# feather_stm32f1.net
KiCad netlist of a schematic drawn in EAGLE
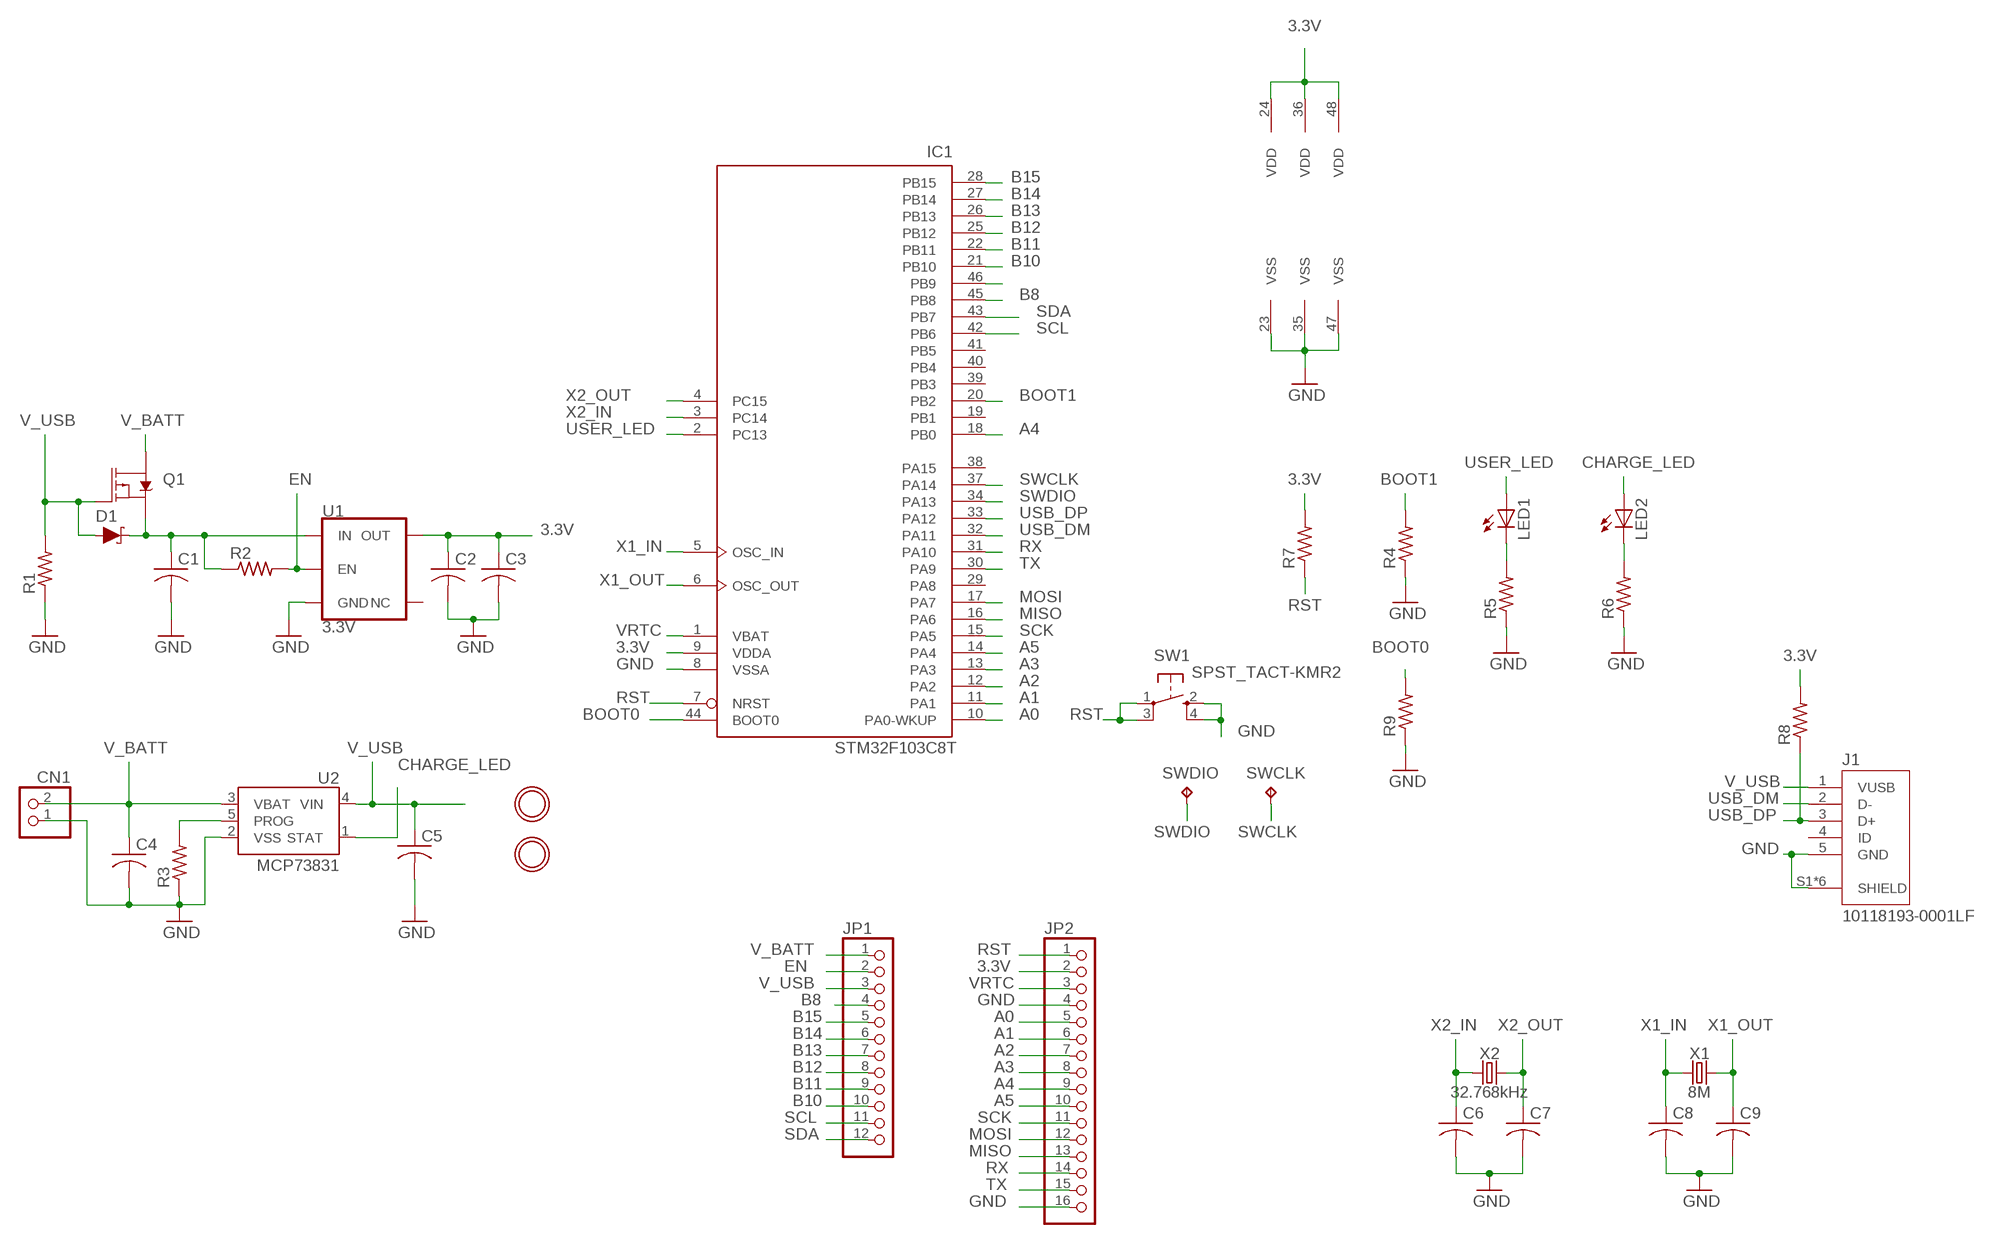
[diagram p0: schematic, sheet 1]

(export (version "E")
  (design (tool "Eeschema 10.0.6"))
  (components
    (comp (ref "C1")
      (value "C-USC0805")
      (footprint "eagle-import:C0805")
      (libsource (lib "eagle-import") (part "C-USC0805"))
    )
    (comp (ref "C2")
      (value "C-USC0805")
      (footprint "eagle-import:C0805")
      (libsource (lib "eagle-import") (part "C-USC0805"))
    )
    (comp (ref "C3")
      (value "C-USC0805")
      (footprint "eagle-import:C0805")
      (libsource (lib "eagle-import") (part "C-USC0805"))
    )
    (comp (ref "C4")
      (value "C-USC0805")
      (footprint "eagle-import:C0805")
      (libsource (lib "eagle-import") (part "C-USC0805"))
    )
    (comp (ref "C5")
      (value "C-USC0805")
      (footprint "eagle-import:C0805")
      (libsource (lib "eagle-import") (part "C-USC0805"))
    )
    (comp (ref "C6")
      (value "C-USC0603")
      (footprint "eagle-import:C0603")
      (libsource (lib "eagle-import") (part "C-USC0603"))
    )
    (comp (ref "C7")
      (value "C-USC0603")
      (footprint "eagle-import:C0603")
      (libsource (lib "eagle-import") (part "C-USC0603"))
    )
    (comp (ref "C8")
      (value "C-USC0603")
      (footprint "eagle-import:C0603")
      (libsource (lib "eagle-import") (part "C-USC0603"))
    )
    (comp (ref "C9")
      (value "C-USC0603")
      (footprint "eagle-import:C0603")
      (libsource (lib "eagle-import") (part "C-USC0603"))
    )
    (comp (ref "CN1")
      (value "JST_2PIN-SMT-RA")
      (footprint "eagle-import:JST-PH-2-SMT-RA")
      (libsource (lib "eagle-import") (part "JST_2PIN-SMT-RA"))
    )
    (comp (ref "D1")
      (value "DIODE-SCHOTTKY-BAT20J")
      (footprint "eagle-import:SOD-323")
      (libsource (lib "eagle-import") (part "DIODE-SCHOTTKY-BAT20J"))
    )
    (comp (ref "IC1")
      (value "STM32F103C8T")
      (footprint "eagle-import:LQFP48")
      (libsource (lib "eagle-import") (part "STM32F103CT8"))
    )
    (comp (ref "J1")
      (value "10118193-0001LF")
      (footprint "eagle-import:FCI_10118193-0001LF")
      (fields (field (name "DIGI-KEY_PART_NUMBER") "609-4616-1-ND") (field (name "MF") "Amphenol ICC"))
      (libsource (lib "eagle-import") (part "10118193-0001LF"))
    )
    (comp (ref "JP1")
      (value "PINHD-1X12-CB")
      (footprint "eagle-import:1X12-CB")
      (libsource (lib "eagle-import") (part "PINHD-1X12-CB"))
    )
    (comp (ref "JP2")
      (value "PINHD16")
      (footprint "eagle-import:1X16-CB")
      (libsource (lib "eagle-import") (part "PINHD16"))
    )
    (comp (ref "LED1")
      (value "LEDCHIPLED_0603")
      (footprint "eagle-import:CHIPLED_0603")
      (libsource (lib "eagle-import") (part "LEDCHIPLED_0603"))
    )
    (comp (ref "LED2")
      (value "LEDCHIPLED_0603")
      (footprint "eagle-import:CHIPLED_0603")
      (libsource (lib "eagle-import") (part "LEDCHIPLED_0603"))
    )
    (comp (ref "Q1")
      (value "MOSFET_PCH-DMG2307L")
      (footprint "eagle-import:SOT23-3")
      (libsource (lib "eagle-import") (part "MOSFET_PCH-DMG2307L"))
    )
    (comp (ref "R1")
      (value "R-US_R0603")
      (footprint "eagle-import:R0603")
      (libsource (lib "eagle-import") (part "R-US_R0603"))
    )
    (comp (ref "R2")
      (value "R-US_R0603")
      (footprint "eagle-import:R0603")
      (libsource (lib "eagle-import") (part "R-US_R0603"))
    )
    (comp (ref "R3")
      (value "R-US_R0603")
      (footprint "eagle-import:R0603")
      (libsource (lib "eagle-import") (part "R-US_R0603"))
    )
    (comp (ref "R4")
      (value "R-US_R0603")
      (footprint "eagle-import:R0603")
      (libsource (lib "eagle-import") (part "R-US_R0603"))
    )
    (comp (ref "R5")
      (value "R-US_R0603")
      (footprint "eagle-import:R0603")
      (libsource (lib "eagle-import") (part "R-US_R0603"))
    )
    (comp (ref "R6")
      (value "R-US_R0603")
      (footprint "eagle-import:R0603")
      (libsource (lib "eagle-import") (part "R-US_R0603"))
    )
    (comp (ref "R7")
      (value "R-US_R0603")
      (footprint "eagle-import:R0603")
      (libsource (lib "eagle-import") (part "R-US_R0603"))
    )
    (comp (ref "R8")
      (value "R-US_R0603")
      (footprint "eagle-import:R0603")
      (libsource (lib "eagle-import") (part "R-US_R0603"))
    )
    (comp (ref "R9")
      (value "R-US_R0603")
      (footprint "eagle-import:R0603")
      (libsource (lib "eagle-import") (part "R-US_R0603"))
    )
    (comp (ref "SW1")
      (value "SPST_TACT-KMR2")
      (footprint "eagle-import:KMR2")
      (libsource (lib "eagle-import") (part "SPST_TACT-KMR2"))
    )
    (comp (ref "SWCLK")
      (value "TPTP20R")
      (footprint "eagle-import:TP20R")
      (libsource (lib "eagle-import") (part "TPTP20R"))
    )
    (comp (ref "SWDIO")
      (value "TPTP20R")
      (footprint "eagle-import:TP20R")
      (libsource (lib "eagle-import") (part "TPTP20R"))
    )
    (comp (ref "U$1")
      (value "MOUNTINGHOLE2.5")
      (footprint "eagle-import:MOUNTINGHOLE_2.5_PLATED")
      (libsource (lib "eagle-import") (part "MOUNTINGHOLE2.5"))
    )
    (comp (ref "U$31")
      (value "MOUNTINGHOLE2.5")
      (footprint "eagle-import:MOUNTINGHOLE_2.5_PLATED")
      (libsource (lib "eagle-import") (part "MOUNTINGHOLE2.5"))
    )
    (comp (ref "U1")
      (value "3.3V")
      (footprint "eagle-import:SOT23-5")
      (libsource (lib "eagle-import") (part "V_REG_AP2112K-3.3V"))
    )
    (comp (ref "U2")
      (value "MCP73831")
      (footprint "eagle-import:SOT23-5")
      (libsource (lib "eagle-import") (part "MCP73831"))
    )
    (comp (ref "X1")
      (value "8M")
      (footprint "eagle-import:CRYSTAL-SMD-5X3.2-2PAD")
      (libsource (lib "eagle-import") (part "CRYSTALSMD-5X3.2-2PAD"))
    )
    (comp (ref "X2")
      (value "32.768kHz")
      (footprint "eagle-import:CRYSTAL-SMD-3.2X1.5MM")
      (libsource (lib "eagle-import") (part "CRYSTAL-32.768KHZSMD-3.2X1.5"))
    )
  )
  (nets
    (net (code "1") (name "/3.3V") (class "Default")
      (node (ref "C2") (pin "1") (pinfunction "1_1") (pintype "passive"))
      (node (ref "C3") (pin "1") (pinfunction "1_1") (pintype "passive"))
      (node (ref "IC1") (pin "24") (pinfunction "VDD_24") (pintype "power_in"))
      (node (ref "IC1") (pin "36") (pinfunction "VDD_36") (pintype "power_in"))
      (node (ref "IC1") (pin "48") (pinfunction "VDD_48") (pintype "power_in"))
      (node (ref "IC1") (pin "9") (pinfunction "VDDA_9") (pintype "power_in"))
      (node (ref "JP2") (pin "2") (pinfunction "2_2") (pintype "passive"))
      (node (ref "R7") (pin "2") (pinfunction "2_2") (pintype "passive"))
      (node (ref "R8") (pin "2") (pinfunction "2_2") (pintype "passive"))
      (node (ref "U1") (pin "5") (pinfunction "OUT_5") (pintype "passive"))
    )
    (net (code "2") (name "/A0") (class "Default")
      (node (ref "IC1") (pin "10") (pinfunction "PA0-WKUP_10") (pintype "bidirectional"))
      (node (ref "JP2") (pin "5") (pinfunction "5_5") (pintype "passive"))
    )
    (net (code "3") (name "/A1") (class "Default")
      (node (ref "IC1") (pin "11") (pinfunction "PA1_11") (pintype "bidirectional"))
      (node (ref "JP2") (pin "6") (pinfunction "6_6") (pintype "passive"))
    )
    (net (code "4") (name "/A2") (class "Default")
      (node (ref "IC1") (pin "12") (pinfunction "PA2_12") (pintype "bidirectional"))
      (node (ref "JP2") (pin "7") (pinfunction "7_7") (pintype "passive"))
    )
    (net (code "5") (name "/A3") (class "Default")
      (node (ref "IC1") (pin "13") (pinfunction "PA3_13") (pintype "bidirectional"))
      (node (ref "JP2") (pin "8") (pinfunction "8_8") (pintype "passive"))
    )
    (net (code "6") (name "/A4") (class "Default")
      (node (ref "IC1") (pin "18") (pinfunction "PB0_18") (pintype "bidirectional"))
      (node (ref "JP2") (pin "9") (pinfunction "9_9") (pintype "passive"))
    )
    (net (code "7") (name "/A5") (class "Default")
      (node (ref "IC1") (pin "14") (pinfunction "PA4_14") (pintype "bidirectional"))
      (node (ref "JP2") (pin "10") (pinfunction "10_10") (pintype "passive"))
    )
    (net (code "8") (name "/B8") (class "Default")
      (node (ref "IC1") (pin "45") (pinfunction "PB8_45") (pintype "bidirectional"))
      (node (ref "JP1") (pin "4") (pinfunction "4_4") (pintype "passive"))
    )
    (net (code "9") (name "/B10") (class "Default")
      (node (ref "IC1") (pin "21") (pinfunction "PB10_21") (pintype "bidirectional"))
      (node (ref "JP1") (pin "10") (pinfunction "10_10") (pintype "passive"))
    )
    (net (code "10") (name "/B11") (class "Default")
      (node (ref "IC1") (pin "22") (pinfunction "PB11_22") (pintype "bidirectional"))
      (node (ref "JP1") (pin "9") (pinfunction "9_9") (pintype "passive"))
    )
    (net (code "11") (name "/B12") (class "Default")
      (node (ref "IC1") (pin "25") (pinfunction "PB12_25") (pintype "bidirectional"))
      (node (ref "JP1") (pin "8") (pinfunction "8_8") (pintype "passive"))
    )
    (net (code "12") (name "/B13") (class "Default")
      (node (ref "IC1") (pin "26") (pinfunction "PB13_26") (pintype "bidirectional"))
      (node (ref "JP1") (pin "7") (pinfunction "7_7") (pintype "passive"))
    )
    (net (code "13") (name "/B14") (class "Default")
      (node (ref "IC1") (pin "27") (pinfunction "PB14_27") (pintype "bidirectional"))
      (node (ref "JP1") (pin "6") (pinfunction "6_6") (pintype "passive"))
    )
    (net (code "14") (name "/B15") (class "Default")
      (node (ref "IC1") (pin "28") (pinfunction "PB15_28") (pintype "bidirectional"))
      (node (ref "JP1") (pin "5") (pinfunction "5_5") (pintype "passive"))
    )
    (net (code "15") (name "/BOOT0") (class "Default")
      (node (ref "IC1") (pin "44") (pinfunction "BOOT0_44") (pintype "input"))
      (node (ref "R9") (pin "2") (pinfunction "2_2") (pintype "passive"))
    )
    (net (code "16") (name "/BOOT1") (class "Default")
      (node (ref "IC1") (pin "20") (pinfunction "PB2_20") (pintype "bidirectional"))
      (node (ref "R4") (pin "2") (pinfunction "2_2") (pintype "passive"))
    )
    (net (code "17") (name "/CHARGE_LED") (class "Default")
      (node (ref "LED2") (pin "A") (pinfunction "A_A") (pintype "passive"))
      (node (ref "U2") (pin "1") (pinfunction "STAT_1") (pintype "output"))
    )
    (net (code "18") (name "/EN") (class "Default")
      (node (ref "JP1") (pin "2") (pinfunction "2_2") (pintype "passive"))
      (node (ref "R2") (pin "2") (pinfunction "2_2") (pintype "passive"))
      (node (ref "U1") (pin "3") (pinfunction "EN_3") (pintype "input"))
    )
    (net (code "19") (name "/MISO") (class "Default")
      (node (ref "IC1") (pin "16") (pinfunction "PA6_16") (pintype "bidirectional"))
      (node (ref "JP2") (pin "13") (pinfunction "13_13") (pintype "passive"))
    )
    (net (code "20") (name "/MOSI") (class "Default")
      (node (ref "IC1") (pin "17") (pinfunction "PA7_17") (pintype "bidirectional"))
      (node (ref "JP2") (pin "12") (pinfunction "12_12") (pintype "passive"))
    )
    (net (code "21") (name "/RST") (class "Default")
      (node (ref "IC1") (pin "7") (pinfunction "NRST_7") (pintype "bidirectional"))
      (node (ref "JP2") (pin "1") (pinfunction "1_1") (pintype "passive"))
      (node (ref "R7") (pin "1") (pinfunction "1_1") (pintype "passive"))
      (node (ref "SW1") (pin "1") (pinfunction "P_1") (pintype "passive"))
      (node (ref "SW1") (pin "3") (pinfunction "P1_3") (pintype "passive"))
    )
    (net (code "22") (name "/RX") (class "Default")
      (node (ref "IC1") (pin "31") (pinfunction "PA10_31") (pintype "bidirectional"))
      (node (ref "JP2") (pin "14") (pinfunction "14_14") (pintype "passive"))
    )
    (net (code "23") (name "/SCK") (class "Default")
      (node (ref "IC1") (pin "15") (pinfunction "PA5_15") (pintype "bidirectional"))
      (node (ref "JP2") (pin "11") (pinfunction "11_11") (pintype "passive"))
    )
    (net (code "24") (name "/SCL") (class "Default")
      (node (ref "IC1") (pin "42") (pinfunction "PB6_42") (pintype "bidirectional"))
      (node (ref "JP1") (pin "11") (pinfunction "11_11") (pintype "passive"))
    )
    (net (code "25") (name "/SDA") (class "Default")
      (node (ref "IC1") (pin "43") (pinfunction "PB7_43") (pintype "bidirectional"))
      (node (ref "JP1") (pin "12") (pinfunction "12_12") (pintype "passive"))
    )
    (net (code "26") (name "/SWCLK") (class "Default")
      (node (ref "IC1") (pin "37") (pinfunction "PA14_37") (pintype "bidirectional"))
      (node (ref "SWCLK") (pin "TP") (pinfunction "TP_TP") (pintype "input"))
    )
    (net (code "27") (name "/SWDIO") (class "Default")
      (node (ref "IC1") (pin "34") (pinfunction "PA13_34") (pintype "bidirectional"))
      (node (ref "SWDIO") (pin "TP") (pinfunction "TP_TP") (pintype "input"))
    )
    (net (code "28") (name "/TX") (class "Default")
      (node (ref "IC1") (pin "30") (pinfunction "PA9_30") (pintype "bidirectional"))
      (node (ref "JP2") (pin "15") (pinfunction "15_15") (pintype "passive"))
    )
    (net (code "29") (name "/USB_DM") (class "Default")
      (node (ref "IC1") (pin "32") (pinfunction "PA11_32") (pintype "bidirectional"))
      (node (ref "J1") (pin "2") (pinfunction "D-_2") (pintype "passive"))
    )
    (net (code "30") (name "/USB_DP") (class "Default")
      (node (ref "IC1") (pin "33") (pinfunction "PA12_33") (pintype "bidirectional"))
      (node (ref "J1") (pin "3") (pinfunction "D+_3") (pintype "passive"))
      (node (ref "R8") (pin "1") (pinfunction "1_1") (pintype "passive"))
    )
    (net (code "31") (name "/USER_LED") (class "Default")
      (node (ref "IC1") (pin "2") (pinfunction "PC13_2") (pintype "bidirectional"))
      (node (ref "LED1") (pin "A") (pinfunction "A_A") (pintype "passive"))
    )
    (net (code "32") (name "/VRTC") (class "Default")
      (node (ref "IC1") (pin "1") (pinfunction "VBAT_1") (pintype "power_in"))
      (node (ref "JP2") (pin "3") (pinfunction "3_3") (pintype "passive"))
    )
    (net (code "33") (name "/V_BATT") (class "Default")
      (node (ref "C4") (pin "1") (pinfunction "1_1") (pintype "passive"))
      (node (ref "CN1") (pin "2") (pinfunction "1_2") (pintype "passive"))
      (node (ref "JP1") (pin "1") (pinfunction "1_1") (pintype "passive"))
      (node (ref "Q1") (pin "3") (pinfunction "D_3") (pintype "bidirectional"))
      (node (ref "U2") (pin "3") (pinfunction "VBAT_3") (pintype "power_in"))
    )
    (net (code "34") (name "/V_USB") (class "Default")
      (node (ref "C5") (pin "1") (pinfunction "1_1") (pintype "passive"))
      (node (ref "D1") (pin "A") (pinfunction "A_A") (pintype "passive"))
      (node (ref "J1") (pin "1") (pinfunction "VUSB_1") (pintype "passive"))
      (node (ref "JP1") (pin "3") (pinfunction "3_3") (pintype "passive"))
      (node (ref "Q1") (pin "1") (pinfunction "G_1") (pintype "bidirectional"))
      (node (ref "R1") (pin "2") (pinfunction "2_2") (pintype "passive"))
      (node (ref "U2") (pin "4") (pinfunction "VIN_4") (pintype "power_in"))
    )
    (net (code "35") (name "/X1_IN") (class "Default")
      (node (ref "C8") (pin "1") (pinfunction "1_1") (pintype "passive"))
      (node (ref "IC1") (pin "5") (pinfunction "OSC_IN_5") (pintype "bidirectional"))
      (node (ref "X1") (pin "P$1") (pinfunction "1_P$1") (pintype "passive"))
    )
    (net (code "36") (name "/X1_OUT") (class "Default")
      (node (ref "C9") (pin "1") (pinfunction "1_1") (pintype "passive"))
      (node (ref "IC1") (pin "6") (pinfunction "OSC_OUT_6") (pintype "bidirectional"))
      (node (ref "X1") (pin "P$2") (pinfunction "2_P$2") (pintype "passive"))
    )
    (net (code "37") (name "/X2_IN") (class "Default")
      (node (ref "C6") (pin "1") (pinfunction "1_1") (pintype "passive"))
      (node (ref "IC1") (pin "3") (pinfunction "PC14_3") (pintype "bidirectional"))
      (node (ref "X2") (pin "P$1") (pinfunction "1_P$1") (pintype "passive"))
    )
    (net (code "38") (name "/X2_OUT") (class "Default")
      (node (ref "C7") (pin "1") (pinfunction "1_1") (pintype "passive"))
      (node (ref "IC1") (pin "4") (pinfunction "PC15_4") (pintype "bidirectional"))
      (node (ref "X2") (pin "P$2") (pinfunction "2_P$2") (pintype "passive"))
    )
    (net (code "39") (name "GND") (class "Default")
      (node (ref "C1") (pin "2") (pinfunction "2_2") (pintype "passive"))
      (node (ref "C2") (pin "2") (pinfunction "2_2") (pintype "passive"))
      (node (ref "C3") (pin "2") (pinfunction "2_2") (pintype "passive"))
      (node (ref "C4") (pin "2") (pinfunction "2_2") (pintype "passive"))
      (node (ref "C5") (pin "2") (pinfunction "2_2") (pintype "passive"))
      (node (ref "C6") (pin "2") (pinfunction "2_2") (pintype "passive"))
      (node (ref "C7") (pin "2") (pinfunction "2_2") (pintype "passive"))
      (node (ref "C8") (pin "2") (pinfunction "2_2") (pintype "passive"))
      (node (ref "C9") (pin "2") (pinfunction "2_2") (pintype "passive"))
      (node (ref "CN1") (pin "1") (pinfunction "2_1") (pintype "passive"))
      (node (ref "IC1") (pin "23") (pinfunction "VSS_23") (pintype "power_in"))
      (node (ref "IC1") (pin "35") (pinfunction "VSS_35") (pintype "power_in"))
      (node (ref "IC1") (pin "47") (pinfunction "VSS_47") (pintype "power_in"))
      (node (ref "IC1") (pin "8") (pinfunction "VSSA_8") (pintype "power_in"))
      (node (ref "J1") (pin "5") (pinfunction "GND_5") (pintype "passive"))
      (node (ref "J1") (pin "S1") (pinfunction "SHIELD_S1") (pintype "passive"))
      (node (ref "J1") (pin "S2") (pinfunction "SHIELD_S2") (pintype "passive"))
      (node (ref "J1") (pin "S3") (pinfunction "SHIELD_S3") (pintype "passive"))
      (node (ref "J1") (pin "S4") (pinfunction "SHIELD_S4") (pintype "passive"))
      (node (ref "J1") (pin "S5") (pinfunction "SHIELD_S5") (pintype "passive"))
      (node (ref "J1") (pin "S6") (pinfunction "SHIELD_S6") (pintype "passive"))
      (node (ref "JP2") (pin "16") (pinfunction "16_16") (pintype "passive"))
      (node (ref "JP2") (pin "4") (pinfunction "4_4") (pintype "passive"))
      (node (ref "R1") (pin "1") (pinfunction "1_1") (pintype "passive"))
      (node (ref "R3") (pin "1") (pinfunction "1_1") (pintype "passive"))
      (node (ref "R4") (pin "1") (pinfunction "1_1") (pintype "passive"))
      (node (ref "R5") (pin "1") (pinfunction "1_1") (pintype "passive"))
      (node (ref "R6") (pin "1") (pinfunction "1_1") (pintype "passive"))
      (node (ref "R9") (pin "1") (pinfunction "1_1") (pintype "passive"))
      (node (ref "SW1") (pin "2") (pinfunction "S_2") (pintype "passive"))
      (node (ref "SW1") (pin "4") (pinfunction "S1_4") (pintype "passive"))
      (node (ref "U1") (pin "2") (pinfunction "GND_2") (pintype "input"))
      (node (ref "U2") (pin "2") (pinfunction "VSS_2") (pintype "power_in"))
    )
    (net (code "40") (name "Net-(LED1-PadC)") (class "Default")
      (node (ref "LED1") (pin "C") (pinfunction "C_C") (pintype "passive"))
      (node (ref "R5") (pin "2") (pinfunction "2_2") (pintype "passive"))
    )
    (net (code "41") (name "Net-(LED2-PadC)") (class "Default")
      (node (ref "LED2") (pin "C") (pinfunction "C_C") (pintype "passive"))
      (node (ref "R6") (pin "2") (pinfunction "2_2") (pintype "passive"))
    )
    (net (code "42") (name "Net-(Q1-S)") (class "Default")
      (node (ref "C1") (pin "1") (pinfunction "1_1") (pintype "passive"))
      (node (ref "D1") (pin "C") (pinfunction "C_C") (pintype "passive"))
      (node (ref "Q1") (pin "2") (pinfunction "S_2") (pintype "bidirectional"))
      (node (ref "R2") (pin "1") (pinfunction "1_1") (pintype "passive"))
      (node (ref "U1") (pin "1") (pinfunction "IN_1") (pintype "input"))
    )
    (net (code "43") (name "Net-(U2-PROG)") (class "Default")
      (node (ref "R3") (pin "2") (pinfunction "2_2") (pintype "passive"))
      (node (ref "U2") (pin "5") (pinfunction "PROG_5") (pintype "input"))
    )
    (net (code "44") (name "unconnected-(IC1A-PA8-Pad29)") (class "Default")
      (node (ref "IC1") (pin "29") (pinfunction "PA8_29") (pintype "bidirectional"))
    )
    (net (code "45") (name "unconnected-(IC1A-PA15-Pad38)") (class "Default")
      (node (ref "IC1") (pin "38") (pinfunction "PA15_38") (pintype "bidirectional"))
    )
    (net (code "46") (name "unconnected-(IC1A-PB1-Pad19)") (class "Default")
      (node (ref "IC1") (pin "19") (pinfunction "PB1_19") (pintype "bidirectional"))
    )
    (net (code "47") (name "unconnected-(IC1A-PB3-Pad39)") (class "Default")
      (node (ref "IC1") (pin "39") (pinfunction "PB3_39") (pintype "bidirectional"))
    )
    (net (code "48") (name "unconnected-(IC1A-PB4-Pad40)") (class "Default")
      (node (ref "IC1") (pin "40") (pinfunction "PB4_40") (pintype "bidirectional"))
    )
    (net (code "49") (name "unconnected-(IC1A-PB5-Pad41)") (class "Default")
      (node (ref "IC1") (pin "41") (pinfunction "PB5_41") (pintype "bidirectional"))
    )
    (net (code "50") (name "unconnected-(IC1A-PB9-Pad46)") (class "Default")
      (node (ref "IC1") (pin "46") (pinfunction "PB9_46") (pintype "bidirectional"))
    )
    (net (code "51") (name "unconnected-(J1-ID-Pad4)") (class "Default")
      (node (ref "J1") (pin "4") (pinfunction "ID_4") (pintype "passive"))
    )
    (net (code "52") (name "unconnected-(U1-NC-Pad4)") (class "Default")
      (node (ref "U1") (pin "4") (pinfunction "NC_4") (pintype "no_connect"))
    )
  )
)
